# TIDA-010967_DC_Regulators.net
KiCad netlist of a schematic drawn in Altium Designer
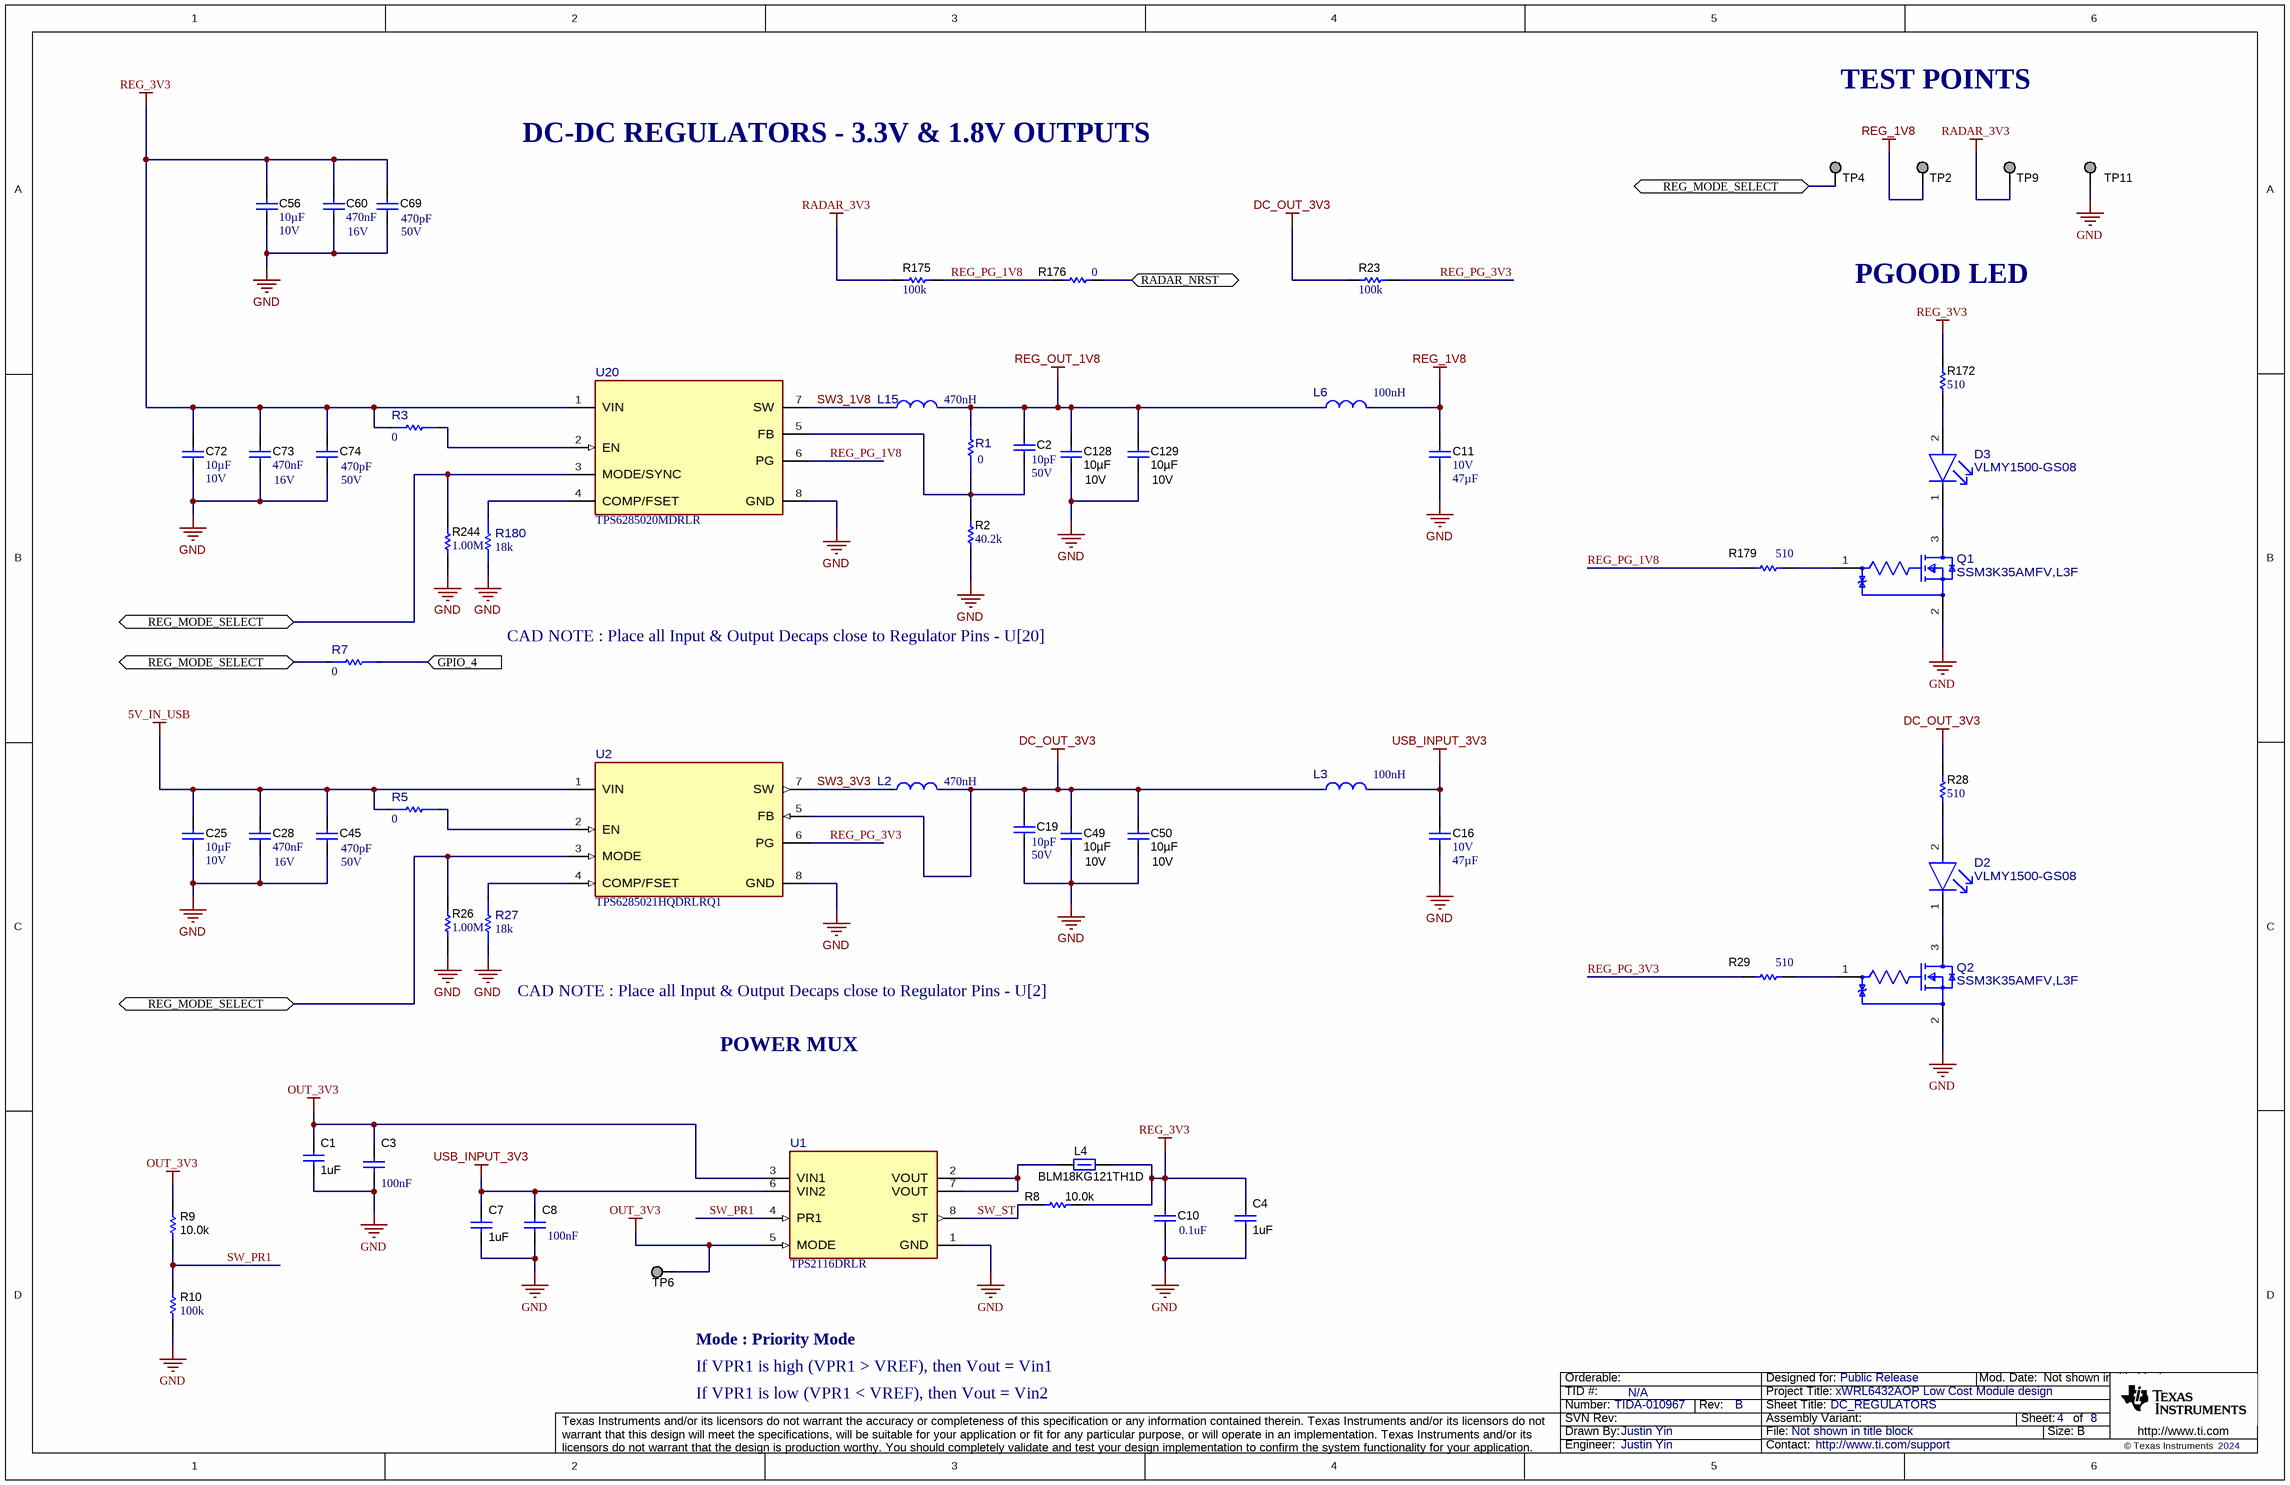
[diagram p0: TIDA-010967_DC_Regulators.SchDoc]

(export (version "E")
  (design (tool "Eeschema 10.0.6"))
  (components
    (comp (ref "C1")
      (value "GRT155C81A105KE01D")
      (footprint "0402L")
      (description "CAP, CERM, 1 uF, 10 V, +/- 10%, X6S, 0402")
      (fields
        (field (name "VALUEDISPLAYED") "1uF")
        (field (name "MANUFACTURER") "TDK")
        (field (name "PUBLISHER") "Texas Instruments")
      )
      (libsource (lib "Altium Vault - TI") (part "Capacitor"))
    )
    (comp (ref "C2")
      (value "GRM1555C1H100JA01D")
      (footprint "0402L")
      (description "CAP, CERM, 10 pF, 50 V, +/- 5%, C0G/NP0, 0402")
      (fields
        (field (name "MANUFACTURER") "MuRata")
        (field (name "VDC_V") "50V")
        (field (name "VALUEDISPLAYED") "10pF")
        (field (name "PUBLISHER") "Texas Instruments")
      )
      (libsource (lib "Altium Vault - TI") (part "Capacitor"))
    )
    (comp (ref "C3")
      (value "GCM155R71H104KE02D")
      (footprint "0402")
      (description "CAP, CERM, 0.1 uF, 50 V, +/- 10%, X7R, AEC-Q200 Grade 1, 0402")
      (fields
        (field (name "CAP_F") "100nF")
        (field (name "MANUFACTURER") "MuRata")
        (field (name "PUBLISHER") "Texas Instruments")
      )
      (libsource (lib "Altium Vault - TI") (part "Capacitor"))
    )
    (comp (ref "C4")
      (value "GRT155C81A105KE01D")
      (footprint "0402L")
      (description "CAP, CERM, 1 uF, 10 V, +/- 10%, X6S, 0402")
      (fields
        (field (name "VALUEDISPLAYED") "1uF")
        (field (name "MANUFACTURER") "TDK")
        (field (name "PUBLISHER") "Texas Instruments")
      )
      (libsource (lib "Altium Vault - TI") (part "Capacitor"))
    )
    (comp (ref "C7")
      (value "GRT155C81A105KE01D")
      (footprint "0402L")
      (description "CAP, CERM, 1 uF, 10 V, +/- 10%, X6S, 0402")
      (fields
        (field (name "VALUEDISPLAYED") "1uF")
        (field (name "MANUFACTURER") "TDK")
        (field (name "PUBLISHER") "Texas Instruments")
      )
      (libsource (lib "Altium Vault - TI") (part "Capacitor"))
    )
    (comp (ref "C8")
      (value "GCM155R71H104KE02D")
      (footprint "0402")
      (description "CAP, CERM, 0.1 uF, 50 V, +/- 10%, X7R, AEC-Q200 Grade 1, 0402")
      (fields
        (field (name "CAP_F") "100nF")
        (field (name "MANUFACTURER") "MuRata")
        (field (name "PUBLISHER") "Texas Instruments")
      )
      (libsource (lib "Altium Vault - TI") (part "Capacitor"))
    )
    (comp (ref "C10")
      (value "GCM155R71H104KE02D")
      (footprint "0402")
      (description "CAP, CERM, 0.1 uF, 50 V, +/- 10%, X7R, AEC-Q200 Grade 1, 0402")
      (fields
        (field (name "MANUFACTURER") "MuRata")
        (field (name "VALUEDISPLAYED") "0.1uF")
        (field (name "PUBLISHER") "Texas Instruments")
      )
      (libsource (lib "Altium Vault - TI") (part "Capacitor"))
    )
    (comp (ref "C11")
      (value "GRM21BR61A476ME15L")
      (footprint "0805_HV")
      (description "CAP, CERM, 47 µF, 10 V,+/- 20%, X5R, 0805")
      (fields
        (field (name "MANUFACTURER") "MuRata")
        (field (name "VDC_V") "10V")
        (field (name "VALUEDISPLAYED") "47µF")
      )
      (libsource (lib "Altium Vault - TI") (part "Capacitor"))
    )
    (comp (ref "C16")
      (value "GRM21BR61A476ME15L")
      (footprint "0805_HV")
      (description "CAP, CERM, 47 µF, 10 V,+/- 20%, X5R, 0805")
      (fields
        (field (name "MANUFACTURER") "MuRata")
        (field (name "VDC_V") "10V")
        (field (name "VALUEDISPLAYED") "47µF")
      )
      (libsource (lib "Altium Vault - TI") (part "Capacitor"))
    )
    (comp (ref "C19")
      (value "GRM1555C1H100JA01D")
      (footprint "0402L")
      (description "CAP, CERM, 10 pF, 50 V, +/- 5%, C0G/NP0, 0402")
      (fields
        (field (name "MANUFACTURER") "MuRata")
        (field (name "VDC_V") "50V")
        (field (name "VALUEDISPLAYED") "10pF")
        (field (name "PUBLISHER") "Texas Instruments")
      )
      (libsource (lib "Altium Vault - TI") (part "Capacitor"))
    )
    (comp (ref "C25")
      (value "GRM188Z71A106MA73D")
      (footprint "0603_HV")
      (description "CAP, CERM, 10 uF, 10 V, +/- 20%, X7R, 0603")
      (fields
        (field (name "MANUFACTURER") "MuRata")
        (field (name "CAP_F") "10µF")
        (field (name "VDC_V") "10V")
        (field (name "PUBLISHER") "Texas Instruments")
      )
      (libsource (lib "Altium Vault - TI") (part "Capacitor"))
    )
    (comp (ref "C28")
      (value "GRM188R71C474KA88D")
      (footprint "0603L")
      (description "CAP, CERM, 0.47 uF, 16 V, +/- 10%, X7R, 0603")
      (fields
        (field (name "MANUFACTURER") "MuRata")
        (field (name "VALUE2") "16V")
        (field (name "CAP_F") "470nF")
        (field (name "PUBLISHER") "Texas Instruments")
      )
      (libsource (lib "Altium Vault - TI") (part "Capacitor"))
    )
    (comp (ref "C45")
      (value "GRM1555C1H471JA01D")
      (footprint "0402L")
      (description "CAP, CERM, 470 pF, 50 V, +/- 5%, C0G/NP0, 0402")
      (fields
        (field (name "MANUFACTURER") "MuRata")
        (field (name "VALUE2") "50V")
        (field (name "VALUEDISPLAYED") "470pF")
        (field (name "PUBLISHER") "Texas Instruments")
      )
      (libsource (lib "Altium Vault - TI") (part "Capacitor"))
    )
    (comp (ref "C49")
      (value "GRM188Z71A106MA73D")
      (footprint "0603L")
      (description "CAP, CERM, 10 uF, 10 V, +/- 20%, X7R, 0603")
      (fields
        (field (name "MANUFACTURER") "MuRata")
        (field (name "VALUE2") "10V")
        (field (name "CAP_F") "10µF")
        (field (name "PUBLISHER") "Texas Instruments")
      )
      (libsource (lib "Altium Vault - TI") (part "Capacitor"))
    )
    (comp (ref "C50")
      (value "GRM188Z71A106MA73D")
      (footprint "0603L")
      (description "CAP, CERM, 10 uF, 10 V, +/- 20%, X7R, 0603")
      (fields
        (field (name "MANUFACTURER") "MuRata")
        (field (name "VALUE2") "10V")
        (field (name "CAP_F") "10µF")
        (field (name "PUBLISHER") "Texas Instruments")
      )
      (libsource (lib "Altium Vault - TI") (part "Capacitor"))
    )
    (comp (ref "C56")
      (value "GRM188Z71A106MA73D")
      (footprint "0603_HV")
      (description "CAP, CERM, 10 uF, 10 V, +/- 20%, X7R, 0603")
      (fields
        (field (name "MANUFACTURER") "MuRata")
        (field (name "CAP_F") "10µF")
        (field (name "VDC_V") "10V")
        (field (name "PUBLISHER") "Texas Instruments")
      )
      (libsource (lib "Altium Vault - TI") (part "Capacitor"))
    )
    (comp (ref "C60")
      (value "GRM188R71C474KA88D")
      (footprint "0603L")
      (description "CAP, CERM, 0.47 uF, 16 V, +/- 10%, X7R, 0603")
      (fields
        (field (name "MANUFACTURER") "MuRata")
        (field (name "VALUE2") "16V")
        (field (name "CAP_F") "470nF")
        (field (name "PUBLISHER") "Texas Instruments")
      )
      (libsource (lib "Altium Vault - TI") (part "Capacitor"))
    )
    (comp (ref "C69")
      (value "GRM1555C1H471JA01D")
      (footprint "0402L")
      (description "CAP, CERM, 470 pF, 50 V, +/- 5%, C0G/NP0, 0402")
      (fields
        (field (name "MANUFACTURER") "MuRata")
        (field (name "VALUE2") "50V")
        (field (name "VALUEDISPLAYED") "470pF")
        (field (name "PUBLISHER") "Texas Instruments")
      )
      (libsource (lib "Altium Vault - TI") (part "Capacitor"))
    )
    (comp (ref "C72")
      (value "GRM188Z71A106MA73D")
      (footprint "0603_HV")
      (description "CAP, CERM, 10 uF, 10 V, +/- 20%, X7R, 0603")
      (fields
        (field (name "MANUFACTURER") "MuRata")
        (field (name "CAP_F") "10µF")
        (field (name "VDC_V") "10V")
        (field (name "PUBLISHER") "Texas Instruments")
      )
      (libsource (lib "Altium Vault - TI") (part "Capacitor"))
    )
    (comp (ref "C73")
      (value "GRM188R71C474KA88D")
      (footprint "0603L")
      (description "CAP, CERM, 0.47 uF, 16 V, +/- 10%, X7R, 0603")
      (fields
        (field (name "MANUFACTURER") "MuRata")
        (field (name "VALUE2") "16V")
        (field (name "CAP_F") "470nF")
        (field (name "PUBLISHER") "Texas Instruments")
      )
      (libsource (lib "Altium Vault - TI") (part "Capacitor"))
    )
    (comp (ref "C74")
      (value "GRM1555C1H471JA01D")
      (footprint "0402L")
      (description "CAP, CERM, 470 pF, 50 V, +/- 5%, C0G/NP0, 0402")
      (fields
        (field (name "MANUFACTURER") "MuRata")
        (field (name "VALUE2") "50V")
        (field (name "VALUEDISPLAYED") "470pF")
        (field (name "PUBLISHER") "Texas Instruments")
      )
      (libsource (lib "Altium Vault - TI") (part "Capacitor"))
    )
    (comp (ref "C128")
      (value "GRM188Z71A106MA73D")
      (footprint "0603L")
      (description "CAP, CERM, 10 uF, 10 V, +/- 20%, X7R, 0603")
      (fields
        (field (name "MANUFACTURER") "MuRata")
        (field (name "VALUE2") "10V")
        (field (name "CAP_F") "10µF")
        (field (name "PUBLISHER") "Texas Instruments")
      )
      (libsource (lib "Altium Vault - TI") (part "Capacitor"))
    )
    (comp (ref "C129")
      (value "GRM188Z71A106MA73D")
      (footprint "0603L")
      (description "CAP, CERM, 10 uF, 10 V, +/- 20%, X7R, 0603")
      (fields
        (field (name "MANUFACTURER") "MuRata")
        (field (name "VALUE2") "10V")
        (field (name "CAP_F") "10µF")
        (field (name "PUBLISHER") "Texas Instruments")
      )
      (libsource (lib "Altium Vault - TI") (part "Capacitor"))
    )
    (comp (ref "D2")
      (value "VLMY1500-GS08")
      (footprint "FP-VLMY1500-GS08_0402-MFG")
      (description "LED Uni-Color Yellow 588nm 2-Pin Chip 0402(1006Metric) T/R")
      (fields (field (name "MOUSER PART NUMBER") "78-VLMY1500-GS08") (field (name "MANUFACTURER") "Vishay"))
      (libsource (lib "Altium Vault - TI") (part "SYM-VLMY1500-GS08"))
    )
    (comp (ref "D3")
      (value "VLMY1500-GS08")
      (footprint "FP-VLMY1500-GS08_0402-MFG")
      (description "LED Uni-Color Yellow 588nm 2-Pin Chip 0402(1006Metric) T/R")
      (fields (field (name "MOUSER PART NUMBER") "78-VLMY1500-GS08") (field (name "MANUFACTURER") "Vishay"))
      (libsource (lib "Altium Vault - TI") (part "SYM-VLMY1500-GS08"))
    )
    (comp (ref "L2")
      (value "DFE201210U-R47M=P2")
      (footprint "FP-DFE201210U-R47M=P2_0805 (2012)-MFG")
      (description "470nH Shielded Wirewound Inductor 3A 42mOhm Max 0805 (2012 Metric)")
      (fields
        (field (name "MOUSER PART NUMBER") "81-DFE201210U-R47MP2")
        (field (name "IND_H") "470nH")
        (field (name "DIGIKEY PART NUMBER") "490-17727-1-ND")
      )
      (libsource (lib "Altium Vault - TI") (part "SYM-DFE201210U-R47M=P2"))
    )
    (comp (ref "L3")
      (value "SPH201610UR10MT")
      (footprint "FP-SPH201610UR10MT_SMT_IND_2MM0_1MM6-MFG")
      (description "100 nH Shielded Drum Core, Wirewound Inductor 3.65 A 22mOhm Max 0806 (2016 Metric)")
      (fields
        (field (name "IND_H") "100nH")
        (field (name "MANUFACTURER") "Sunlord")
        (field (name "DIGIKEY PART NUMBER") "3442-SPH201610UR10MTTR-ND")
      )
      (libsource (lib "Altium Vault - TI") (part "SYM-SPH201610UR10MT"))
    )
    (comp (ref "L4")
      (value "BLM18KG121TH1D")
      (footprint "0603L")
      (description "Ferrite Bead, 120 ohm @ 100 MHz, 1.9 A, 0603")
      (fields (field (name "MANUFACTURER") "MuRata"))
      (libsource (lib "Altium Vault - TI") (part "Ferrite_Bead"))
    )
    (comp (ref "L6")
      (value "SPH201610UR10MT")
      (footprint "FP-SPH201610UR10MT_SMT_IND_2MM0_1MM6-MFG")
      (description "100 nH Shielded Drum Core, Wirewound Inductor 3.65 A 22mOhm Max 0806 (2016 Metric)")
      (fields
        (field (name "IND_H") "100nH")
        (field (name "MANUFACTURER") "Sunlord")
        (field (name "DIGIKEY PART NUMBER") "3442-SPH201610UR10MTTR-ND")
      )
      (libsource (lib "Altium Vault - TI") (part "SYM-SPH201610UR10MT"))
    )
    (comp (ref "L15")
      (value "DFE201210U-R47M=P2")
      (footprint "FP-DFE201210U-R47M=P2_0805 (2012)-MFG")
      (description "470nH Shielded Wirewound Inductor 3A 42mOhm Max 0805 (2012 Metric)")
      (fields
        (field (name "MOUSER PART NUMBER") "81-DFE201210U-R47MP2")
        (field (name "IND_H") "470nH")
        (field (name "DIGIKEY PART NUMBER") "490-17727-1-ND")
      )
      (libsource (lib "Altium Vault - TI") (part "SYM-DFE201210U-R47M=P2"))
    )
    (comp (ref "Q1")
      (value "SSM3K35AMFV,L3F")
      (footprint "FP-SSM3K35AMFV,L3F_SOT-723-MFG")
      (description "N-Channel 20V 250mA (Ta) 500mW (Ta) Surface Mount VESM")
      (fields
        (field (name "MOUSER PART NUMBER") "757-SSM3K35AMFVL3F")
        (field (name "MANUFACTURER") "Toshiba")
      )
      (libsource (lib "Altium Vault - TI") (part "SYM-SSM3K35AMFV,L3F"))
    )
    (comp (ref "Q2")
      (value "SSM3K35AMFV,L3F")
      (footprint "FP-SSM3K35AMFV,L3F_SOT-723-MFG")
      (description "N-Channel 20V 250mA (Ta) 500mW (Ta) Surface Mount VESM")
      (fields
        (field (name "MOUSER PART NUMBER") "757-SSM3K35AMFVL3F")
        (field (name "MANUFACTURER") "Toshiba")
      )
      (libsource (lib "Altium Vault - TI") (part "SYM-SSM3K35AMFV,L3F"))
    )
    (comp (ref "R1")
      (value "0")
      (footprint "FP-RC0402JR-070RP_0402-MFG")
      (description "Res Jumper Thick Film 0402 0 Ohm 5% 1/16W Molded SMD Paper T/R")
      (fields (field (name "MOUSER PART NUMBER") "603-RC0402JR-070RP") (field (name "MANUFACTURER") "Yageo"))
      (libsource (lib "Altium Vault - TI") (part "SYM-RC0402JR-070RP"))
    )
    (comp (ref "R2")
      (value "CRCW040240K2FKED")
      (footprint "0402L")
      (description "RES, 40.2 k, 1%, 0.063 W, AEC-Q200 Grade 0, 0402")
      (fields (field (name "MANUFACTURER") "Vishay-Dale") (field (name "VALUEDISPLAYED") "40.2k"))
      (libsource (lib "Altium Vault - TI") (part "Resistor"))
    )
    (comp (ref "R3")
      (value "0")
      (footprint "FP-RC0402JR-070RP_0402-MFG")
      (description "Res Jumper Thick Film 0402 0 Ohm 5% 1/16W Molded SMD Paper T/R")
      (fields (field (name "MOUSER PART NUMBER") "603-RC0402JR-070RP") (field (name "MANUFACTURER") "Yageo"))
      (libsource (lib "Altium Vault - TI") (part "SYM-RC0402JR-070RP"))
    )
    (comp (ref "R5")
      (value "0")
      (footprint "FP-RC0402JR-070RP_0402-MFG")
      (description "Res Jumper Thick Film 0402 0 Ohm 5% 1/16W Molded SMD Paper T/R")
      (fields (field (name "MOUSER PART NUMBER") "603-RC0402JR-070RP") (field (name "MANUFACTURER") "Yageo"))
      (libsource (lib "Altium Vault - TI") (part "SYM-RC0402JR-070RP"))
    )
    (comp (ref "R7")
      (value "0")
      (footprint "FP-RC0402JR-070RP_0402-MFG")
      (description "Res Jumper Thick Film 0402 0 Ohm 5% 1/16W Molded SMD Paper T/R")
      (fields (field (name "MOUSER PART NUMBER") "603-RC0402JR-070RP") (field (name "MANUFACTURER") "Yageo"))
      (libsource (lib "Altium Vault - TI") (part "SYM-RC0402JR-070RP"))
    )
    (comp (ref "R8")
      (value "CRCW040210K0FKED")
      (footprint "0402L")
      (description "RES, 10.0 k, 1%, 0.063 W, AEC-Q200 Grade 0, 0402")
      (fields (field (name "MANUFACTURER") "Vishay-Dale") (field (name "VALUEDISPLAYED") "10.0k"))
      (libsource (lib "Altium Vault - TI") (part "Resistor"))
    )
    (comp (ref "R9")
      (value "CRCW040210K0FKED")
      (footprint "0402L")
      (description "RES, 10.0 k, 1%, 0.063 W, AEC-Q200 Grade 0, 0402")
      (fields (field (name "MANUFACTURER") "Vishay-Dale") (field (name "VALUEDISPLAYED") "10.0k"))
      (libsource (lib "Altium Vault - TI") (part "Resistor"))
    )
    (comp (ref "R10")
      (value "100k")
      (footprint "0402")
      (description "RES, 100 k, 1%, 0.063 W, AEC-Q200 Grade 0, 0402")
      (fields (field (name "MANUFACTURER") "Vishay-Dale") (field (name "PARTNUMBER") "CRCW0402100KFKED"))
      (libsource (lib "Altium Vault - TI") (part "Resistor"))
    )
    (comp (ref "R23")
      (value "100k")
      (footprint "0201L")
      (description "RES, 100 k, 1%, 0.05 W, 0201")
      (fields (field (name "MANUFACTURER") "Vishay-Dale") (field (name "PARTNUMBER") "CRCW0201100KFKED"))
      (libsource (lib "Altium Vault - TI") (part "Resistor"))
    )
    (comp (ref "R26")
      (value "RC0402FR-071ML")
      (footprint "0402")
      (description "RES, 1.00 M, 1%, 0.063 W, 0402")
      (fields
        (field (name "MANUFACTURER") "Yageo America")
        (field (name "VALUEDISPLAYED") "1.00M")
        (field (name "PUBLISHER") "Texas Instruments")
      )
      (libsource (lib "Altium Vault - TI") (part "Resistor"))
    )
    (comp (ref "R27")
      (value "18k")
      (footprint "FP-CRCW040218K0FKEDC_0402-MFG")
      (description "Res Thick Film 0402 18K Ohm 1% 1/16W ±100ppm/°C Molded SMD Paper T/R")
      (fields (field (name "PART NUMBER") "CRCW040218K0FKEDC") (field (name "MANUFACTURER") "Vishay"))
      (libsource (lib "Altium Vault - TI") (part "SYM-CRCW040218K0FKEDC"))
    )
    (comp (ref "R28")
      (value "ERJ-2RKF5100X")
      (footprint "0402L")
      (description "RES, 510, 1%, 0.1 W, 0402")
      (fields
        (field (name "MANUFACTURER") "Panasonic")
        (field (name "VALUEDISPLAYED") "510")
        (field (name "PUBLISHER") "Texas Instruments")
      )
      (libsource (lib "Altium Vault - TI") (part "Resistor"))
    )
    (comp (ref "R29")
      (value "ERJ-2RKF5100X")
      (footprint "0402L")
      (description "RES, 510, 1%, 0.1 W, 0402")
      (fields
        (field (name "MANUFACTURER") "Panasonic")
        (field (name "VALUEDISPLAYED") "510")
        (field (name "PUBLISHER") "Texas Instruments")
      )
      (libsource (lib "Altium Vault - TI") (part "Resistor"))
    )
    (comp (ref "R172")
      (value "ERJ-2RKF5100X")
      (footprint "0402L")
      (description "RES, 510, 1%, 0.1 W, 0402")
      (fields
        (field (name "MANUFACTURER") "Panasonic")
        (field (name "VALUEDISPLAYED") "510")
        (field (name "PUBLISHER") "Texas Instruments")
      )
      (libsource (lib "Altium Vault - TI") (part "Resistor"))
    )
    (comp (ref "R175")
      (value "100k")
      (footprint "0201L")
      (description "RES, 100 k, 1%, 0.05 W, 0201")
      (fields (field (name "MANUFACTURER") "Vishay-Dale") (field (name "PARTNUMBER") "CRCW0201100KFKED"))
      (libsource (lib "Altium Vault - TI") (part "Resistor"))
    )
    (comp (ref "R176")
      (value "RC0201JR-070RL")
      (footprint "FP-RC0201JR-070RL_0201 (0603 Metric)-IPC_C")
      (description "RES SMD 0 OHM JUMPER 1/20W 0201")
      (fields (field (name "MANUFACTURER") "Yageo") (field (name "RES_OHM") "0"))
      (libsource (lib "Altium Vault - TI") (part "SYM-WSR3R1500F"))
    )
    (comp (ref "R179")
      (value "ERJ-2RKF5100X")
      (footprint "0402L")
      (description "RES, 510, 1%, 0.1 W, 0402")
      (fields
        (field (name "MANUFACTURER") "Panasonic")
        (field (name "VALUEDISPLAYED") "510")
        (field (name "PUBLISHER") "Texas Instruments")
      )
      (libsource (lib "Altium Vault - TI") (part "Resistor"))
    )
    (comp (ref "R180")
      (value "18k")
      (footprint "FP-CRCW040218K0FKEDC_0402-MFG")
      (description "Res Thick Film 0402 18K Ohm 1% 1/16W ±100ppm/°C Molded SMD Paper T/R")
      (fields (field (name "PART NUMBER") "CRCW040218K0FKEDC") (field (name "MANUFACTURER") "Vishay"))
      (libsource (lib "Altium Vault - TI") (part "SYM-CRCW040218K0FKEDC"))
    )
    (comp (ref "R244")
      (value "RC0402FR-071ML")
      (footprint "0402")
      (description "RES, 1.00 M, 1%, 0.063 W, 0402")
      (fields
        (field (name "MANUFACTURER") "Yageo America")
        (field (name "VALUEDISPLAYED") "1.00M")
        (field (name "PUBLISHER") "Texas Instruments")
      )
      (libsource (lib "Altium Vault - TI") (part "Resistor"))
    )
    (comp (ref "TP2")
      (value "TESTPOINT")
      (footprint "TP_25MIL-SMT")
      (description "TEST POINT.  No entry in BOM.")
      (libsource (lib "Altium Vault - TI") (part "TESTPOINT"))
    )
    (comp (ref "TP4")
      (value "TESTPOINT")
      (footprint "TP_25MIL-SMT")
      (description "TEST POINT.  No entry in BOM.")
      (libsource (lib "Altium Vault - TI") (part "TESTPOINT"))
    )
    (comp (ref "TP6")
      (value "TESTPOINT")
      (footprint "TP_25MIL-SMT")
      (description "TEST POINT.  No entry in BOM.")
      (libsource (lib "Altium Vault - TI") (part "TESTPOINT"))
    )
    (comp (ref "TP9")
      (value "TESTPOINT")
      (footprint "TP_25MIL-SMT")
      (description "TEST POINT.  No entry in BOM.")
      (libsource (lib "Altium Vault - TI") (part "TESTPOINT"))
    )
    (comp (ref "TP11")
      (value "TESTPOINT")
      (footprint "TP_25MIL-SMT")
      (description "TEST POINT.  No entry in BOM.")
      (libsource (lib "Altium Vault - TI") (part "TESTPOINT"))
    )
    (comp (ref "U1")
      (value "TPS2116DRLR")
      (footprint "DRL0008A-MFG")
      (description "1.6 V to 5 V, 2.5-A Low IQ Power Mux With Manual and Automatic Switchover")
      (fields (field (name "MANUFACTURER") "Texas Instruments") (field (name "PARTNUMBER") "TPS2116DRLR"))
      (libsource (lib "Altium Vault - TI") (part "SYM-TPS2116DRLR"))
    )
    (comp (ref "U2")
      (value "TPS6285021HQDRLRQ1")
      (footprint "DRL0008A-MFG")
      (description "2.7-V to 6-V, 2-A Automotive Step-Down Converter in SOT583 Package")
      (fields
        (field (name "PARTNUMBER") "TPS6285021HQDRLRQ1")
        (field (name "MANUFACTURER") "Texas Instruments")
      )
      (libsource (lib "Altium Vault - TI") (part "SYM-TPS628502QDRLRQ1"))
    )
    (comp (ref "U20")
      (value "TPS6285020MDRLR")
      (footprint "DRL0008A-MFG")
      (description "2.7-V to 6-V, 2-A Step-Down Converter in SOT583 Package")
      (fields (field (name "MANUFACTURER") "Texas Instruments") (field (name "PARTNUMBER") "TPS6285020MDRLR"))
      (libsource (lib "Altium Vault - TI") (part "SYM-TPS6285020MDRLR"))
    )
  )
  (nets
    (net (code "1") (name "/GPIO_4") (class "Default")
      (node (ref "R7") (pin "1") (pinfunction "1_1") (pintype "passive"))
    )
    (net (code "2") (name "/RADAR_NRST") (class "Default")
      (node (ref "R176") (pin "1") (pinfunction "1_1") (pintype "passive"))
    )
    (net (code "3") (name "/REG_MODE_SELECT") (class "Default")
      (node (ref "R244") (pin "1") (pinfunction "1_1") (pintype "passive"))
      (node (ref "R26") (pin "1") (pinfunction "1_1") (pintype "passive"))
      (node (ref "R7") (pin "2") (pinfunction "2_2") (pintype "passive"))
      (node (ref "TP4") (pin "1") (pintype "passive"))
      (node (ref "U2") (pin "3") (pinfunction "MODE_3") (pintype "input"))
      (node (ref "U20") (pin "3") (pinfunction "MODE/SYNC_3") (pintype "passive"))
    )
    (net (code "4") (name "/REG_PG_1V8") (class "Default")
      (node (ref "R175") (pin "2") (pinfunction "2_2") (pintype "passive"))
      (node (ref "R176") (pin "2") (pinfunction "2_2") (pintype "passive"))
      (node (ref "R179") (pin "2") (pinfunction "2_2") (pintype "passive"))
      (node (ref "U20") (pin "6") (pinfunction "PG_6") (pintype "open_collector"))
    )
    (net (code "5") (name "/REG_PG_3V3") (class "Default")
      (node (ref "R23") (pin "2") (pinfunction "2_2") (pintype "passive"))
      (node (ref "R29") (pin "2") (pinfunction "2_2") (pintype "passive"))
      (node (ref "U2") (pin "6") (pinfunction "PG_6") (pintype "open_collector"))
    )
    (net (code "6") (name "/SW3_1V8") (class "Default")
      (node (ref "L15") (pin "1") (pinfunction "1_1") (pintype "passive"))
      (node (ref "U20") (pin "7") (pinfunction "SW_7") (pintype "passive"))
    )
    (net (code "7") (name "/SW3_3V3") (class "Default")
      (node (ref "L2") (pin "1") (pinfunction "1_1") (pintype "passive"))
      (node (ref "U2") (pin "7") (pinfunction "SW_7") (pintype "output"))
    )
    (net (code "8") (name "/SW_PR1") (class "Default")
      (node (ref "R10") (pin "2") (pinfunction "2_2") (pintype "passive"))
      (node (ref "R9") (pin "1") (pinfunction "1_1") (pintype "passive"))
      (node (ref "U1") (pin "4") (pinfunction "PR1_4") (pintype "input"))
    )
    (net (code "9") (name "/SW_ST") (class "Default")
      (node (ref "R8") (pin "2") (pinfunction "2_2") (pintype "passive"))
      (node (ref "U1") (pin "8") (pinfunction "ST_8") (pintype "output"))
    )
    (net (code "10") (name "5V_IN_USB") (class "Default")
      (node (ref "C25") (pin "1") (pinfunction "1_1") (pintype "passive"))
      (node (ref "C28") (pin "1") (pinfunction "1_1") (pintype "passive"))
      (node (ref "C45") (pin "1") (pinfunction "1_1") (pintype "passive"))
      (node (ref "R5") (pin "2") (pinfunction "2_2") (pintype "passive"))
      (node (ref "U2") (pin "1") (pinfunction "VIN_1") (pintype "power_in"))
    )
    (net (code "11") (name "DC_OUT_3V3") (class "Default")
      (node (ref "C19") (pin "1") (pinfunction "1_1") (pintype "passive"))
      (node (ref "C49") (pin "1") (pinfunction "1_1") (pintype "passive"))
      (node (ref "C50") (pin "1") (pinfunction "1_1") (pintype "passive"))
      (node (ref "L2") (pin "2") (pinfunction "2_2") (pintype "passive"))
      (node (ref "L3") (pin "1") (pinfunction "1_1") (pintype "passive"))
      (node (ref "R23") (pin "1") (pinfunction "1_1") (pintype "passive"))
      (node (ref "R28") (pin "1") (pinfunction "1_1") (pintype "passive"))
      (node (ref "U2") (pin "5") (pinfunction "FB_5") (pintype "input"))
    )
    (net (code "12") (name "GND") (class "Default")
      (node (ref "C1") (pin "2") (pinfunction "2_2") (pintype "passive"))
      (node (ref "C10") (pin "2") (pinfunction "2_2") (pintype "passive"))
      (node (ref "C11") (pin "2") (pinfunction "2_2") (pintype "passive"))
      (node (ref "C128") (pin "2") (pinfunction "2_2") (pintype "passive"))
      (node (ref "C129") (pin "2") (pinfunction "2_2") (pintype "passive"))
      (node (ref "C16") (pin "2") (pinfunction "2_2") (pintype "passive"))
      (node (ref "C19") (pin "2") (pinfunction "2_2") (pintype "passive"))
      (node (ref "C25") (pin "2") (pinfunction "2_2") (pintype "passive"))
      (node (ref "C28") (pin "2") (pinfunction "2_2") (pintype "passive"))
      (node (ref "C3") (pin "2") (pinfunction "2_2") (pintype "passive"))
      (node (ref "C4") (pin "2") (pinfunction "2_2") (pintype "passive"))
      (node (ref "C45") (pin "2") (pinfunction "2_2") (pintype "passive"))
      (node (ref "C49") (pin "2") (pinfunction "2_2") (pintype "passive"))
      (node (ref "C50") (pin "2") (pinfunction "2_2") (pintype "passive"))
      (node (ref "C56") (pin "2") (pinfunction "2_2") (pintype "passive"))
      (node (ref "C60") (pin "2") (pinfunction "2_2") (pintype "passive"))
      (node (ref "C69") (pin "2") (pinfunction "2_2") (pintype "passive"))
      (node (ref "C7") (pin "2") (pinfunction "2_2") (pintype "passive"))
      (node (ref "C72") (pin "2") (pinfunction "2_2") (pintype "passive"))
      (node (ref "C73") (pin "2") (pinfunction "2_2") (pintype "passive"))
      (node (ref "C74") (pin "2") (pinfunction "2_2") (pintype "passive"))
      (node (ref "C8") (pin "1") (pinfunction "1_1") (pintype "passive"))
      (node (ref "Q1") (pin "2") (pinfunction "S_2") (pintype "passive"))
      (node (ref "Q2") (pin "2") (pinfunction "S_2") (pintype "passive"))
      (node (ref "R10") (pin "1") (pinfunction "1_1") (pintype "passive"))
      (node (ref "R180") (pin "2") (pinfunction "2_2") (pintype "passive"))
      (node (ref "R2") (pin "1") (pinfunction "1_1") (pintype "passive"))
      (node (ref "R244") (pin "2") (pinfunction "2_2") (pintype "passive"))
      (node (ref "R26") (pin "2") (pinfunction "2_2") (pintype "passive"))
      (node (ref "R27") (pin "2") (pinfunction "2_2") (pintype "passive"))
      (node (ref "TP11") (pin "1") (pintype "passive"))
      (node (ref "U1") (pin "1") (pinfunction "GND_1") (pintype "power_in"))
      (node (ref "U2") (pin "8") (pinfunction "GND_8") (pintype "power_in"))
      (node (ref "U20") (pin "8") (pinfunction "GND_8") (pintype "power_in"))
    )
    (net (code "13") (name "Net-(D2-ANODE)") (class "Default")
      (node (ref "D2") (pin "2") (pinfunction "ANODE_2") (pintype "passive"))
      (node (ref "R28") (pin "2") (pinfunction "2_2") (pintype "passive"))
    )
    (net (code "14") (name "Net-(D2-CATHODE)") (class "Default")
      (node (ref "D2") (pin "1") (pinfunction "CATHODE_1") (pintype "passive"))
      (node (ref "Q2") (pin "3") (pinfunction "D_3") (pintype "passive"))
    )
    (net (code "15") (name "Net-(D3-ANODE)") (class "Default")
      (node (ref "D3") (pin "2") (pinfunction "ANODE_2") (pintype "passive"))
      (node (ref "R172") (pin "2") (pinfunction "2_2") (pintype "passive"))
    )
    (net (code "16") (name "Net-(D3-CATHODE)") (class "Default")
      (node (ref "D3") (pin "1") (pinfunction "CATHODE_1") (pintype "passive"))
      (node (ref "Q1") (pin "3") (pinfunction "D_3") (pintype "passive"))
    )
    (net (code "17") (name "Net-(L4-Pad1)") (class "Default")
      (node (ref "L4") (pin "1") (pinfunction "1_1") (pintype "passive"))
      (node (ref "U1") (pin "2") (pinfunction "VOUT_2") (pintype "passive"))
      (node (ref "U1") (pin "7") (pinfunction "VOUT_7") (pintype "passive"))
    )
    (net (code "18") (name "Net-(Q1-G)") (class "Default")
      (node (ref "Q1") (pin "1") (pinfunction "G_1") (pintype "passive"))
      (node (ref "R179") (pin "1") (pinfunction "1_1") (pintype "passive"))
    )
    (net (code "19") (name "Net-(Q2-G)") (class "Default")
      (node (ref "Q2") (pin "1") (pinfunction "G_1") (pintype "passive"))
      (node (ref "R29") (pin "1") (pinfunction "1_1") (pintype "passive"))
    )
    (net (code "20") (name "Net-(U2-COMP{slash}FSET)") (class "Default")
      (node (ref "R27") (pin "1") (pinfunction "1_1") (pintype "passive"))
      (node (ref "U2") (pin "4") (pinfunction "COMP/FSET_4") (pintype "input"))
    )
    (net (code "21") (name "Net-(U2-EN)") (class "Default")
      (node (ref "R5") (pin "1") (pinfunction "1_1") (pintype "passive"))
      (node (ref "U2") (pin "2") (pinfunction "EN_2") (pintype "input"))
    )
    (net (code "22") (name "Net-(U20-COMP{slash}FSET)") (class "Default")
      (node (ref "R180") (pin "1") (pinfunction "1_1") (pintype "passive"))
      (node (ref "U20") (pin "4") (pinfunction "COMP/FSET_4") (pintype "passive"))
    )
    (net (code "23") (name "Net-(U20-EN)") (class "Default")
      (node (ref "R3") (pin "1") (pinfunction "1_1") (pintype "passive"))
      (node (ref "U20") (pin "2") (pinfunction "EN_2") (pintype "input"))
    )
    (net (code "24") (name "Net-(U20-FB)") (class "Default")
      (node (ref "C2") (pin "2") (pinfunction "2_2") (pintype "passive"))
      (node (ref "R1") (pin "1") (pinfunction "1_1") (pintype "passive"))
      (node (ref "R2") (pin "2") (pinfunction "2_2") (pintype "passive"))
      (node (ref "U20") (pin "5") (pinfunction "FB_5") (pintype "passive"))
    )
    (net (code "25") (name "OUT_3V3") (class "Default")
      (node (ref "C1") (pin "1") (pinfunction "1_1") (pintype "passive"))
      (node (ref "C3") (pin "1") (pinfunction "1_1") (pintype "passive"))
      (node (ref "R9") (pin "2") (pinfunction "2_2") (pintype "passive"))
      (node (ref "TP6") (pin "1") (pintype "passive"))
      (node (ref "U1") (pin "3") (pinfunction "VIN1_3") (pintype "power_in"))
      (node (ref "U1") (pin "5") (pinfunction "MODE_5") (pintype "input"))
    )
    (net (code "26") (name "RADAR_3V3") (class "Default")
      (node (ref "R175") (pin "1") (pinfunction "1_1") (pintype "passive"))
      (node (ref "TP9") (pin "1") (pintype "passive"))
    )
    (net (code "27") (name "REG_1V8") (class "Default")
      (node (ref "C11") (pin "1") (pinfunction "1_1") (pintype "passive"))
      (node (ref "L6") (pin "2") (pinfunction "2_2") (pintype "passive"))
      (node (ref "TP2") (pin "1") (pintype "passive"))
    )
    (net (code "28") (name "REG_3V3") (class "Default")
      (node (ref "C10") (pin "1") (pinfunction "1_1") (pintype "passive"))
      (node (ref "C4") (pin "1") (pinfunction "1_1") (pintype "passive"))
      (node (ref "C56") (pin "1") (pinfunction "1_1") (pintype "passive"))
      (node (ref "C60") (pin "1") (pinfunction "1_1") (pintype "passive"))
      (node (ref "C69") (pin "1") (pinfunction "1_1") (pintype "passive"))
      (node (ref "C72") (pin "1") (pinfunction "1_1") (pintype "passive"))
      (node (ref "C73") (pin "1") (pinfunction "1_1") (pintype "passive"))
      (node (ref "C74") (pin "1") (pinfunction "1_1") (pintype "passive"))
      (node (ref "L4") (pin "2") (pinfunction "2_2") (pintype "passive"))
      (node (ref "R172") (pin "1") (pinfunction "1_1") (pintype "passive"))
      (node (ref "R3") (pin "2") (pinfunction "2_2") (pintype "passive"))
      (node (ref "R8") (pin "1") (pinfunction "1_1") (pintype "passive"))
      (node (ref "U20") (pin "1") (pinfunction "VIN_1") (pintype "power_in"))
    )
    (net (code "29") (name "REG_OUT_1V8") (class "Default")
      (node (ref "C128") (pin "1") (pinfunction "1_1") (pintype "passive"))
      (node (ref "C129") (pin "1") (pinfunction "1_1") (pintype "passive"))
      (node (ref "C2") (pin "1") (pinfunction "1_1") (pintype "passive"))
      (node (ref "L15") (pin "2") (pinfunction "2_2") (pintype "passive"))
      (node (ref "L6") (pin "1") (pinfunction "1_1") (pintype "passive"))
      (node (ref "R1") (pin "2") (pinfunction "2_2") (pintype "passive"))
    )
    (net (code "30") (name "USB_INPUT_3V3") (class "Default")
      (node (ref "C16") (pin "1") (pinfunction "1_1") (pintype "passive"))
      (node (ref "C7") (pin "1") (pinfunction "1_1") (pintype "passive"))
      (node (ref "C8") (pin "2") (pinfunction "2_2") (pintype "passive"))
      (node (ref "L3") (pin "2") (pinfunction "2_2") (pintype "passive"))
      (node (ref "U1") (pin "6") (pinfunction "VIN2_6") (pintype "power_in"))
    )
  )
)
